# AdukiPlus.net
KiCad netlist of a schematic drawn in EAGLE
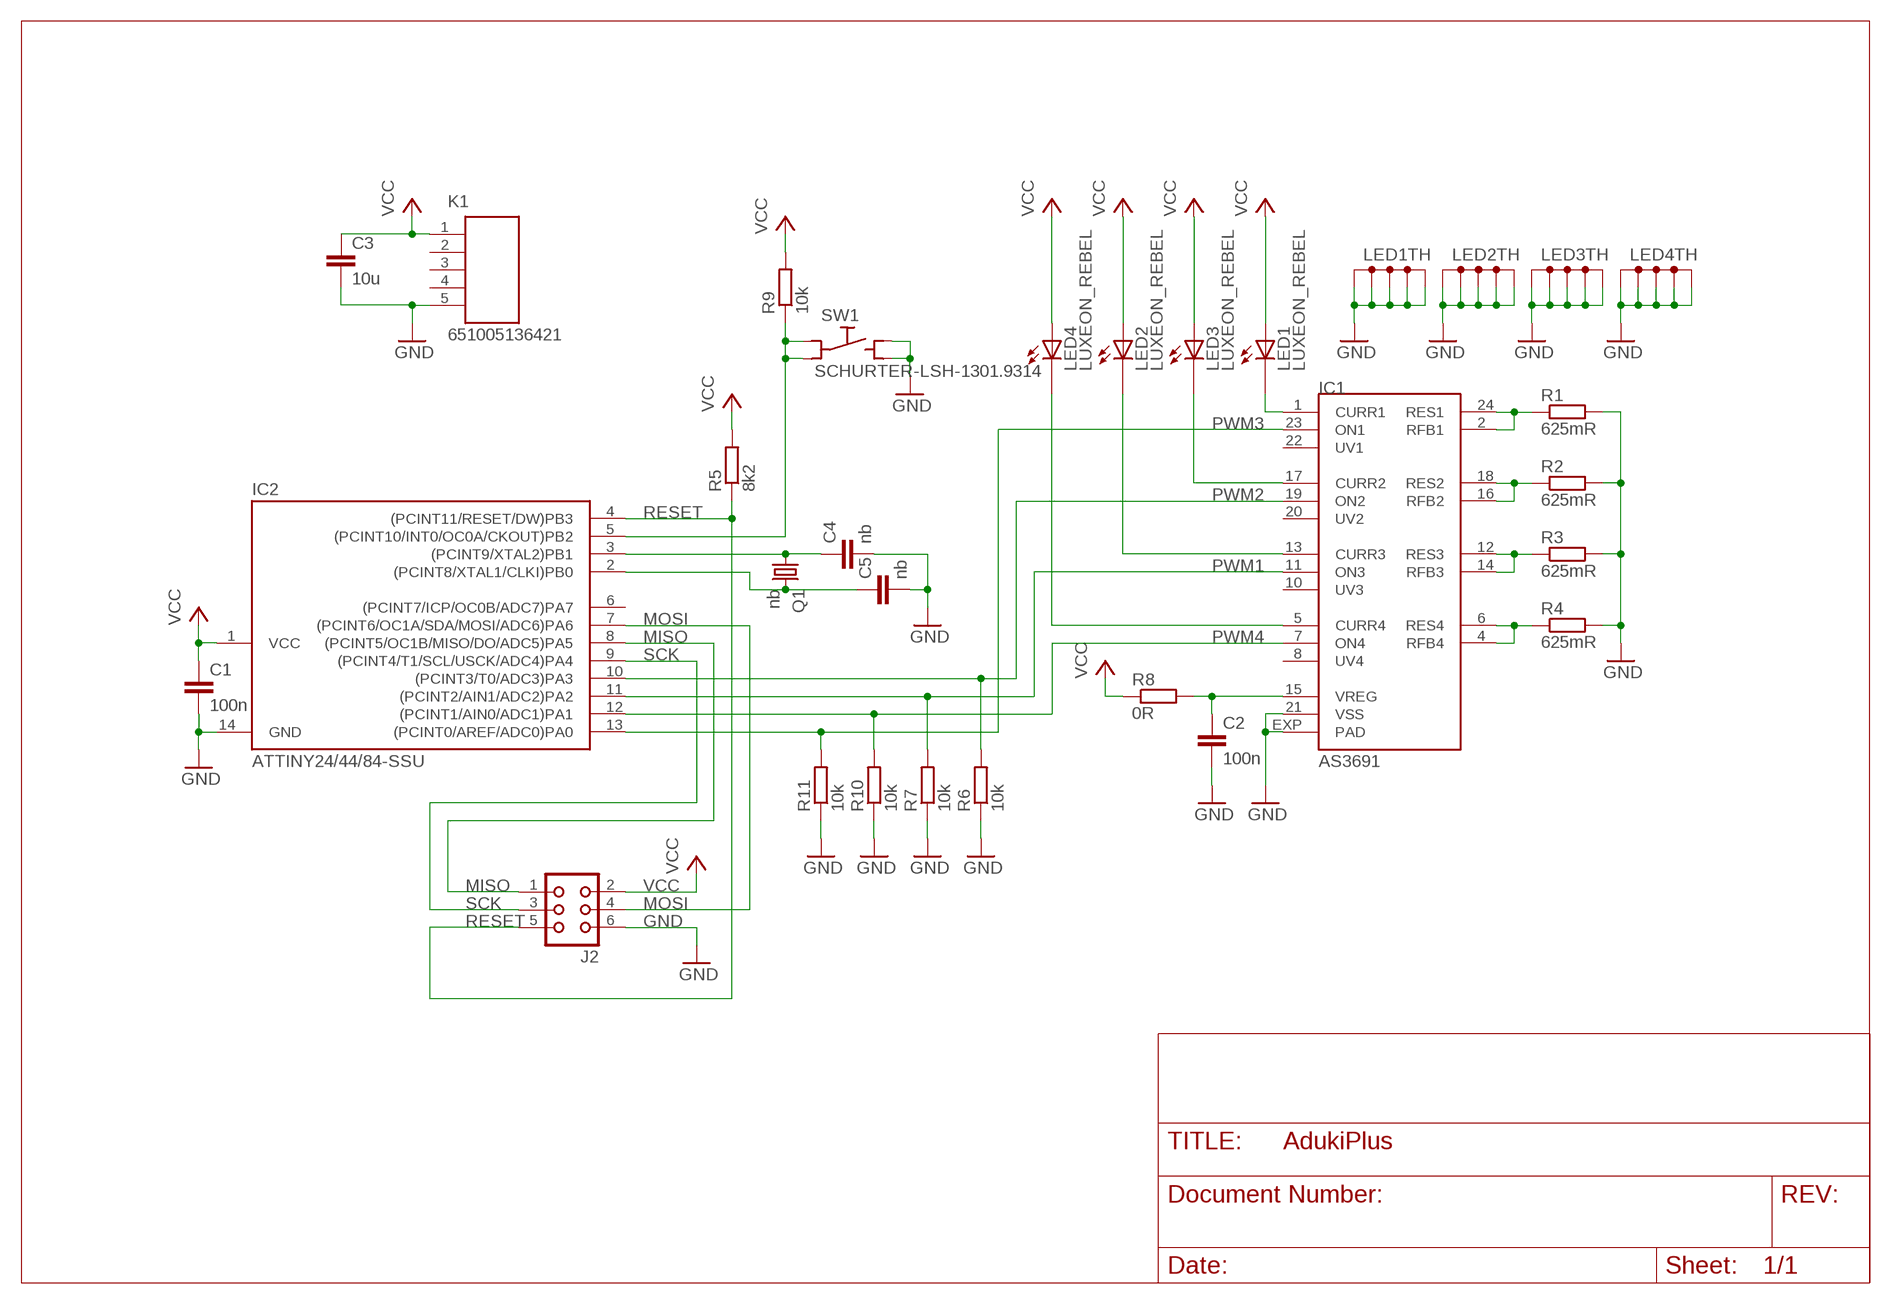
[diagram p0: schematic, sheet 1]

(export (version "E")
  (design (tool "Eeschema 10.0.6"))
  (components
    (comp (ref "C1")
      (value "100n")
      (footprint "eagle-import:C0603")
      (libsource (lib "eagle-import") (part "C-EUC0603"))
    )
    (comp (ref "C2")
      (value "100n")
      (footprint "eagle-import:C0603")
      (libsource (lib "eagle-import") (part "C-EUC0603"))
    )
    (comp (ref "C3")
      (value "10u")
      (footprint "eagle-import:C0603")
      (libsource (lib "eagle-import") (part "C-EUC0603"))
    )
    (comp (ref "C4")
      (value "nb")
      (footprint "eagle-import:C0603")
      (libsource (lib "eagle-import") (part "C-EUC0603"))
    )
    (comp (ref "C5")
      (value "nb")
      (footprint "eagle-import:C0603")
      (libsource (lib "eagle-import") (part "C-EUC0603"))
    )
    (comp (ref "IC1")
      (value "AS3691")
      (footprint "eagle-import:QFN24-4X4")
      (libsource (lib "eagle-import") (part "AS3691"))
    )
    (comp (ref "IC2")
      (value "ATTINY24/44/84-SSU")
      (footprint "eagle-import:SOIC14")
      (libsource (lib "eagle-import") (part "ATTINY24/44/84-SSU"))
    )
    (comp (ref "J2")
      (value "CON06")
      (footprint "eagle-import:CON06")
      (libsource (lib "eagle-import") (part "CON06"))
    )
    (comp (ref "K1")
      (value "651005136421")
      (footprint "eagle-import:651005136421")
      (libsource (lib "eagle-import") (part "651005136421"))
    )
    (comp (ref "LED1")
      (value "LUXEON_REBEL")
      (footprint "eagle-import:LUXEON_REBEL")
      (libsource (lib "eagle-import") (part "LUXEON_REBEL"))
    )
    (comp (ref "LED2")
      (value "LUXEON_REBEL")
      (footprint "eagle-import:LUXEON_REBEL")
      (libsource (lib "eagle-import") (part "LUXEON_REBEL"))
    )
    (comp (ref "LED3")
      (value "LUXEON_REBEL")
      (footprint "eagle-import:LUXEON_REBEL")
      (libsource (lib "eagle-import") (part "LUXEON_REBEL"))
    )
    (comp (ref "LED4")
      (value "LUXEON_REBEL")
      (footprint "eagle-import:LUXEON_REBEL")
      (libsource (lib "eagle-import") (part "LUXEON_REBEL"))
    )
    (comp (ref "Q1")
      (value "nb")
      (footprint "eagle-import:32X25")
      (libsource (lib "eagle-import") (part "QUARZ"))
    )
    (comp (ref "R1")
      (value "625mR")
      (footprint "eagle-import:R0603")
      (libsource (lib "eagle-import") (part "R-EU_R0603"))
    )
    (comp (ref "R2")
      (value "625mR")
      (footprint "eagle-import:R0603")
      (libsource (lib "eagle-import") (part "R-EU_R0603"))
    )
    (comp (ref "R3")
      (value "625mR")
      (footprint "eagle-import:R0603")
      (libsource (lib "eagle-import") (part "R-EU_R0603"))
    )
    (comp (ref "R4")
      (value "625mR")
      (footprint "eagle-import:R0603")
      (libsource (lib "eagle-import") (part "R-EU_R0603"))
    )
    (comp (ref "R5")
      (value "8k2")
      (footprint "eagle-import:R0603")
      (libsource (lib "eagle-import") (part "R-EU_R0603"))
    )
    (comp (ref "R6")
      (value "10k")
      (footprint "eagle-import:R0603")
      (libsource (lib "eagle-import") (part "R-EU_R0603"))
    )
    (comp (ref "R7")
      (value "10k")
      (footprint "eagle-import:R0603")
      (libsource (lib "eagle-import") (part "R-EU_R0603"))
    )
    (comp (ref "R8")
      (value "0R")
      (footprint "eagle-import:R0603")
      (libsource (lib "eagle-import") (part "R-EU_R0603"))
    )
    (comp (ref "R9")
      (value "10k")
      (footprint "eagle-import:R0603")
      (libsource (lib "eagle-import") (part "R-EU_R0603"))
    )
    (comp (ref "R10")
      (value "10k")
      (footprint "eagle-import:R0603")
      (libsource (lib "eagle-import") (part "R-EU_R0603"))
    )
    (comp (ref "R11")
      (value "10k")
      (footprint "eagle-import:R0603")
      (libsource (lib "eagle-import") (part "R-EU_R0603"))
    )
    (comp (ref "SW1")
      (value "SCHURTER-LSH-1301.9314")
      (footprint "eagle-import:LSH")
      (libsource (lib "eagle-import") (part "SCHURTER-LSH-1301.9314"))
    )
  )
  (nets
    (net (code "1") (name "/MISO") (class "Default")
      (node (ref "IC2") (pin "8") (pinfunction "(PCINT5/OC1B/MISO/DO/ADC5)PA5_8") (pintype "bidirectional"))
      (node (ref "J2") (pin "1") (pinfunction "1_1") (pintype "passive"))
    )
    (net (code "2") (name "/MOSI") (class "Default")
      (node (ref "IC2") (pin "7") (pinfunction "(PCINT6/OC1A/SDA/MOSI/ADC6)PA6_7") (pintype "bidirectional"))
      (node (ref "J2") (pin "4") (pinfunction "4_4") (pintype "passive"))
    )
    (net (code "3") (name "/PWM1") (class "Default")
      (node (ref "IC1") (pin "11") (pinfunction "ON3_11") (pintype "input"))
      (node (ref "IC2") (pin "11") (pinfunction "(PCINT2/AIN1/ADC2)PA2_11") (pintype "bidirectional"))
      (node (ref "R7") (pin "2") (pinfunction "2_2") (pintype "passive"))
    )
    (net (code "4") (name "/PWM2") (class "Default")
      (node (ref "IC1") (pin "19") (pinfunction "ON2_19") (pintype "input"))
      (node (ref "IC2") (pin "10") (pinfunction "(PCINT3/T0/ADC3)PA3_10") (pintype "bidirectional"))
      (node (ref "R6") (pin "2") (pinfunction "2_2") (pintype "passive"))
    )
    (net (code "5") (name "/PWM3") (class "Default")
      (node (ref "IC1") (pin "23") (pinfunction "ON1_23") (pintype "input"))
      (node (ref "IC2") (pin "13") (pinfunction "(PCINT0/AREF/ADC0)PA0_13") (pintype "bidirectional"))
      (node (ref "R11") (pin "2") (pinfunction "2_2") (pintype "passive"))
    )
    (net (code "6") (name "/PWM4") (class "Default")
      (node (ref "IC1") (pin "7") (pinfunction "ON4_7") (pintype "input"))
      (node (ref "IC2") (pin "12") (pinfunction "(PCINT1/AIN0/ADC1)PA1_12") (pintype "bidirectional"))
      (node (ref "R10") (pin "2") (pinfunction "2_2") (pintype "passive"))
    )
    (net (code "7") (name "/RESET") (class "Default")
      (node (ref "IC2") (pin "4") (pinfunction "(PCINT11/RESET/DW)PB3_4") (pintype "bidirectional"))
      (node (ref "J2") (pin "5") (pinfunction "5_5") (pintype "passive"))
      (node (ref "R5") (pin "1") (pinfunction "1_1") (pintype "passive"))
    )
    (net (code "8") (name "/SCK") (class "Default")
      (node (ref "IC2") (pin "9") (pinfunction "(PCINT4/T1/SCL/USCK/ADC4)PA4_9") (pintype "bidirectional"))
      (node (ref "J2") (pin "3") (pinfunction "3_3") (pintype "passive"))
    )
    (net (code "9") (name "GND") (class "Default")
      (node (ref "C1") (pin "2") (pinfunction "2_2") (pintype "passive"))
      (node (ref "C2") (pin "2") (pinfunction "2_2") (pintype "passive"))
      (node (ref "C3") (pin "2") (pinfunction "2_2") (pintype "passive"))
      (node (ref "C4") (pin "2") (pinfunction "2_2") (pintype "passive"))
      (node (ref "C5") (pin "2") (pinfunction "2_2") (pintype "passive"))
      (node (ref "IC1") (pin "21") (pinfunction "VSS_21") (pintype "power_in"))
      (node (ref "IC1") (pin "EXP") (pinfunction "PAD_EXP") (pintype "power_in"))
      (node (ref "IC2") (pin "14") (pinfunction "GND_14") (pintype "power_in"))
      (node (ref "J2") (pin "6") (pinfunction "6_6") (pintype "passive"))
      (node (ref "K1") (pin "5") (pinfunction "5_5") (pintype "passive"))
      (node (ref "LED1") (pin "TH") (pinfunction "TH_TH") (pintype "power_in"))
      (node (ref "LED1") (pin "TH@1") (pinfunction "TH_TH@1") (pintype "power_in"))
      (node (ref "LED1") (pin "TH@2") (pinfunction "TH_TH@2") (pintype "power_in"))
      (node (ref "LED1") (pin "TH@3") (pinfunction "TH_TH@3") (pintype "power_in"))
      (node (ref "LED1") (pin "TH@4") (pinfunction "TH_TH@4") (pintype "power_in"))
      (node (ref "LED2") (pin "TH") (pinfunction "TH_TH") (pintype "power_in"))
      (node (ref "LED2") (pin "TH@1") (pinfunction "TH_TH@1") (pintype "power_in"))
      (node (ref "LED2") (pin "TH@2") (pinfunction "TH_TH@2") (pintype "power_in"))
      (node (ref "LED2") (pin "TH@3") (pinfunction "TH_TH@3") (pintype "power_in"))
      (node (ref "LED2") (pin "TH@4") (pinfunction "TH_TH@4") (pintype "power_in"))
      (node (ref "LED3") (pin "TH") (pinfunction "TH_TH") (pintype "power_in"))
      (node (ref "LED3") (pin "TH@1") (pinfunction "TH_TH@1") (pintype "power_in"))
      (node (ref "LED3") (pin "TH@2") (pinfunction "TH_TH@2") (pintype "power_in"))
      (node (ref "LED3") (pin "TH@3") (pinfunction "TH_TH@3") (pintype "power_in"))
      (node (ref "LED3") (pin "TH@4") (pinfunction "TH_TH@4") (pintype "power_in"))
      (node (ref "LED4") (pin "TH") (pinfunction "TH_TH") (pintype "power_in"))
      (node (ref "LED4") (pin "TH@1") (pinfunction "TH_TH@1") (pintype "power_in"))
      (node (ref "LED4") (pin "TH@2") (pinfunction "TH_TH@2") (pintype "power_in"))
      (node (ref "LED4") (pin "TH@3") (pinfunction "TH_TH@3") (pintype "power_in"))
      (node (ref "LED4") (pin "TH@4") (pinfunction "TH_TH@4") (pintype "power_in"))
      (node (ref "R1") (pin "2") (pinfunction "2_2") (pintype "passive"))
      (node (ref "R10") (pin "1") (pinfunction "1_1") (pintype "passive"))
      (node (ref "R11") (pin "1") (pinfunction "1_1") (pintype "passive"))
      (node (ref "R2") (pin "2") (pinfunction "2_2") (pintype "passive"))
      (node (ref "R3") (pin "2") (pinfunction "2_2") (pintype "passive"))
      (node (ref "R4") (pin "2") (pinfunction "2_2") (pintype "passive"))
      (node (ref "R6") (pin "1") (pinfunction "1_1") (pintype "passive"))
      (node (ref "R7") (pin "1") (pinfunction "1_1") (pintype "passive"))
      (node (ref "SW1") (pin "NO1") (pinfunction "NO_NO1") (pintype "passive"))
      (node (ref "SW1") (pin "NO2") (pinfunction "NO_NO2") (pintype "passive"))
    )
    (net (code "10") (name "Net-(IC1-CURR1)") (class "Default")
      (node (ref "IC1") (pin "1") (pinfunction "CURR1_1") (pintype "passive"))
      (node (ref "LED1") (pin "C") (pinfunction "C_C") (pintype "passive"))
    )
    (net (code "11") (name "Net-(IC1-CURR2)") (class "Default")
      (node (ref "IC1") (pin "17") (pinfunction "CURR2_17") (pintype "passive"))
      (node (ref "LED3") (pin "C") (pinfunction "C_C") (pintype "passive"))
    )
    (net (code "12") (name "Net-(IC1-CURR3)") (class "Default")
      (node (ref "IC1") (pin "13") (pinfunction "CURR3_13") (pintype "passive"))
      (node (ref "LED2") (pin "C") (pinfunction "C_C") (pintype "passive"))
    )
    (net (code "13") (name "Net-(IC1-CURR4)") (class "Default")
      (node (ref "IC1") (pin "5") (pinfunction "CURR4_5") (pintype "passive"))
      (node (ref "LED4") (pin "C") (pinfunction "C_C") (pintype "passive"))
    )
    (net (code "14") (name "Net-(IC1-RES1)") (class "Default")
      (node (ref "IC1") (pin "2") (pinfunction "RFB1_2") (pintype "passive"))
      (node (ref "IC1") (pin "24") (pinfunction "RES1_24") (pintype "passive"))
      (node (ref "R1") (pin "1") (pinfunction "1_1") (pintype "passive"))
    )
    (net (code "15") (name "Net-(IC1-RES2)") (class "Default")
      (node (ref "IC1") (pin "16") (pinfunction "RFB2_16") (pintype "passive"))
      (node (ref "IC1") (pin "18") (pinfunction "RES2_18") (pintype "passive"))
      (node (ref "R2") (pin "1") (pinfunction "1_1") (pintype "passive"))
    )
    (net (code "16") (name "Net-(IC1-RES3)") (class "Default")
      (node (ref "IC1") (pin "12") (pinfunction "RES3_12") (pintype "passive"))
      (node (ref "IC1") (pin "14") (pinfunction "RFB3_14") (pintype "passive"))
      (node (ref "R3") (pin "1") (pinfunction "1_1") (pintype "passive"))
    )
    (net (code "17") (name "Net-(IC1-RES4)") (class "Default")
      (node (ref "IC1") (pin "4") (pinfunction "RFB4_4") (pintype "passive"))
      (node (ref "IC1") (pin "6") (pinfunction "RES4_6") (pintype "passive"))
      (node (ref "R4") (pin "1") (pinfunction "1_1") (pintype "passive"))
    )
    (net (code "18") (name "Net-(IC1-VREG)") (class "Default")
      (node (ref "C2") (pin "1") (pinfunction "1_1") (pintype "passive"))
      (node (ref "IC1") (pin "15") (pinfunction "VREG_15") (pintype "power_in"))
      (node (ref "R8") (pin "2") (pinfunction "2_2") (pintype "passive"))
    )
    (net (code "19") (name "Net-(IC2-(PCINT8{slash}XTAL1{slash}CLKI)PB0)") (class "Default")
      (node (ref "C5") (pin "1") (pinfunction "1_1") (pintype "passive"))
      (node (ref "IC2") (pin "2") (pinfunction "(PCINT8/XTAL1/CLKI)PB0_2") (pintype "bidirectional"))
      (node (ref "Q1") (pin "3") (pinfunction "2_3") (pintype "passive"))
    )
    (net (code "20") (name "Net-(IC2-(PCINT9{slash}XTAL2)PB1)") (class "Default")
      (node (ref "C4") (pin "1") (pinfunction "1_1") (pintype "passive"))
      (node (ref "IC2") (pin "3") (pinfunction "(PCINT9/XTAL2)PB1_3") (pintype "bidirectional"))
      (node (ref "Q1") (pin "1") (pinfunction "1_1") (pintype "passive"))
    )
    (net (code "21") (name "Net-(IC2-(PCINT10{slash}INT0{slash}OC0A{slash}CKOUT)PB2)") (class "Default")
      (node (ref "IC2") (pin "5") (pinfunction "(PCINT10/INT0/OC0A/CKOUT)PB2_5") (pintype "bidirectional"))
      (node (ref "R9") (pin "1") (pinfunction "1_1") (pintype "passive"))
      (node (ref "SW1") (pin "C1") (pinfunction "C_C1") (pintype "passive"))
      (node (ref "SW1") (pin "C2") (pinfunction "C_C2") (pintype "passive"))
    )
    (net (code "22") (name "VCC") (class "Default")
      (node (ref "C1") (pin "1") (pinfunction "1_1") (pintype "passive"))
      (node (ref "C3") (pin "1") (pinfunction "1_1") (pintype "passive"))
      (node (ref "IC2") (pin "1") (pinfunction "VCC_1") (pintype "power_in"))
      (node (ref "J2") (pin "2") (pinfunction "2_2") (pintype "passive"))
      (node (ref "K1") (pin "1") (pinfunction "1_1") (pintype "passive"))
      (node (ref "LED1") (pin "A") (pinfunction "A_A") (pintype "passive"))
      (node (ref "LED2") (pin "A") (pinfunction "A_A") (pintype "passive"))
      (node (ref "LED3") (pin "A") (pinfunction "A_A") (pintype "passive"))
      (node (ref "LED4") (pin "A") (pinfunction "A_A") (pintype "passive"))
      (node (ref "R5") (pin "2") (pinfunction "2_2") (pintype "passive"))
      (node (ref "R8") (pin "1") (pinfunction "1_1") (pintype "passive"))
      (node (ref "R9") (pin "2") (pinfunction "2_2") (pintype "passive"))
    )
    (net (code "23") (name "unconnected-(IC1-UV1-Pad22)") (class "Default")
      (node (ref "IC1") (pin "22") (pinfunction "UV1_22") (pintype "input"))
    )
    (net (code "24") (name "unconnected-(IC1-UV2-Pad20)") (class "Default")
      (node (ref "IC1") (pin "20") (pinfunction "UV2_20") (pintype "input"))
    )
    (net (code "25") (name "unconnected-(IC1-UV3-Pad10)") (class "Default")
      (node (ref "IC1") (pin "10") (pinfunction "UV3_10") (pintype "input"))
    )
    (net (code "26") (name "unconnected-(IC1-UV4-Pad8)") (class "Default")
      (node (ref "IC1") (pin "8") (pinfunction "UV4_8") (pintype "input"))
    )
    (net (code "27") (name "unconnected-(IC2-(PCINT7{slash}ICP{slash}OC0B{slash}ADC7)PA7-Pad6)") (class "Default")
      (node (ref "IC2") (pin "6") (pinfunction "(PCINT7/ICP/OC0B/ADC7)PA7_6") (pintype "bidirectional"))
    )
    (net (code "28") (name "unconnected-(K1-Pad2)") (class "Default")
      (node (ref "K1") (pin "2") (pinfunction "2_2") (pintype "passive"))
    )
    (net (code "29") (name "unconnected-(K1-Pad3)") (class "Default")
      (node (ref "K1") (pin "3") (pinfunction "3_3") (pintype "passive"))
    )
    (net (code "30") (name "unconnected-(K1-Pad4)") (class "Default")
      (node (ref "K1") (pin "4") (pinfunction "4_4") (pintype "passive"))
    )
    (net (code "31") (name "unconnected-(LED1A-A-PadA@1)") (class "Default")
      (node (ref "LED1") (pin "A@1") (pinfunction "A_A@1") (pintype "passive"))
    )
    (net (code "32") (name "unconnected-(LED1A-C-PadC@1)") (class "Default")
      (node (ref "LED1") (pin "C@1") (pinfunction "C_C@1") (pintype "passive"))
    )
    (net (code "33") (name "unconnected-(LED2A-A-PadA@1)") (class "Default")
      (node (ref "LED2") (pin "A@1") (pinfunction "A_A@1") (pintype "passive"))
    )
    (net (code "34") (name "unconnected-(LED2A-C-PadC@1)") (class "Default")
      (node (ref "LED2") (pin "C@1") (pinfunction "C_C@1") (pintype "passive"))
    )
    (net (code "35") (name "unconnected-(LED3A-A-PadA@1)") (class "Default")
      (node (ref "LED3") (pin "A@1") (pinfunction "A_A@1") (pintype "passive"))
    )
    (net (code "36") (name "unconnected-(LED3A-C-PadC@1)") (class "Default")
      (node (ref "LED3") (pin "C@1") (pinfunction "C_C@1") (pintype "passive"))
    )
    (net (code "37") (name "unconnected-(LED4A-A-PadA@1)") (class "Default")
      (node (ref "LED4") (pin "A@1") (pinfunction "A_A@1") (pintype "passive"))
    )
    (net (code "38") (name "unconnected-(LED4A-C-PadC@1)") (class "Default")
      (node (ref "LED4") (pin "C@1") (pinfunction "C_C@1") (pintype "passive"))
    )
  )
)
